# WSTL18_ISP.net
KiCad netlist of a schematic drawn in EAGLE
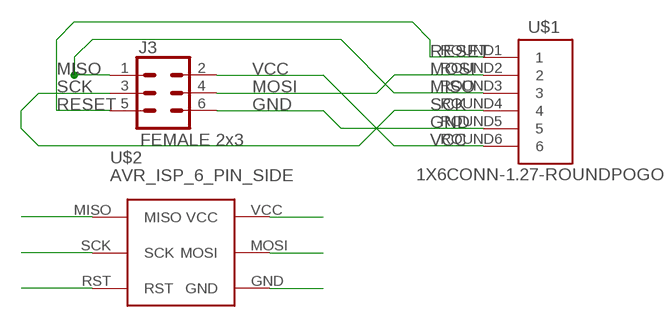
[diagram p0: schematic, sheet 1]

(export (version "E")
  (design (tool "Eeschema 10.0.6"))
  (components
    (comp (ref "J3")
      (value "FEMALE 2x3")
      (footprint "eagle-import:2X3")
      (libsource (lib "eagle-import") (part "CONN_03X2FEMALE"))
    )
    (comp (ref "U$1")
      (value "1X6CONN-1.27-ROUNDPOGO")
      (footprint "eagle-import:1X6_1.27_SIDEPOGO")
      (libsource (lib "eagle-import") (part "1X6CONN-1.27-ROUNDPOGO"))
    )
    (comp (ref "U$2")
      (value "AVR_ISP_6_PIN_SIDE")
      (footprint "eagle-import:AVR_ISP_SIDE_0.1_INCH")
      (libsource (lib "eagle-import") (part "AVR_ISP_6_PIN_SIDE"))
    )
  )
  (nets
    (net (code "1") (name "/GND") (class "Default")
      (node (ref "J3") (pin "6") (pinfunction "6_6") (pintype "bidirectional"))
      (node (ref "U$1") (pin "ROUND5") (pinfunction "5_ROUND5") (pintype "bidirectional"))
      (node (ref "U$2") (pin "GND") (pinfunction "GND_GND") (pintype "bidirectional"))
    )
    (net (code "2") (name "/MISO") (class "Default")
      (node (ref "J3") (pin "1") (pinfunction "1_1") (pintype "bidirectional"))
      (node (ref "U$1") (pin "ROUND3") (pinfunction "3_ROUND3") (pintype "bidirectional"))
      (node (ref "U$2") (pin "MISO") (pinfunction "MISO_MISO") (pintype "bidirectional"))
    )
    (net (code "3") (name "/MOSI") (class "Default")
      (node (ref "J3") (pin "4") (pinfunction "4_4") (pintype "bidirectional"))
      (node (ref "U$1") (pin "ROUND2") (pinfunction "2_ROUND2") (pintype "bidirectional"))
      (node (ref "U$2") (pin "MOSI") (pinfunction "MOSI_MOSI") (pintype "bidirectional"))
    )
    (net (code "4") (name "/RESET") (class "Default")
      (node (ref "J3") (pin "5") (pinfunction "5_5") (pintype "bidirectional"))
      (node (ref "U$1") (pin "ROUND1") (pinfunction "1_ROUND1") (pintype "bidirectional"))
      (node (ref "U$2") (pin "RST") (pinfunction "RST_RST") (pintype "bidirectional"))
    )
    (net (code "5") (name "/SCK") (class "Default")
      (node (ref "J3") (pin "3") (pinfunction "3_3") (pintype "bidirectional"))
      (node (ref "U$1") (pin "ROUND4") (pinfunction "4_ROUND4") (pintype "bidirectional"))
      (node (ref "U$2") (pin "SCK") (pinfunction "SCK_SCK") (pintype "bidirectional"))
    )
    (net (code "6") (name "/VCC") (class "Default")
      (node (ref "J3") (pin "2") (pinfunction "2_2") (pintype "bidirectional"))
      (node (ref "U$1") (pin "ROUND6") (pinfunction "6_ROUND6") (pintype "bidirectional"))
      (node (ref "U$2") (pin "VCC") (pinfunction "VCC_VCC") (pintype "bidirectional"))
    )
  )
)
